# Test_Mux.net
KiCad netlist of a schematic drawn in Altium Designer
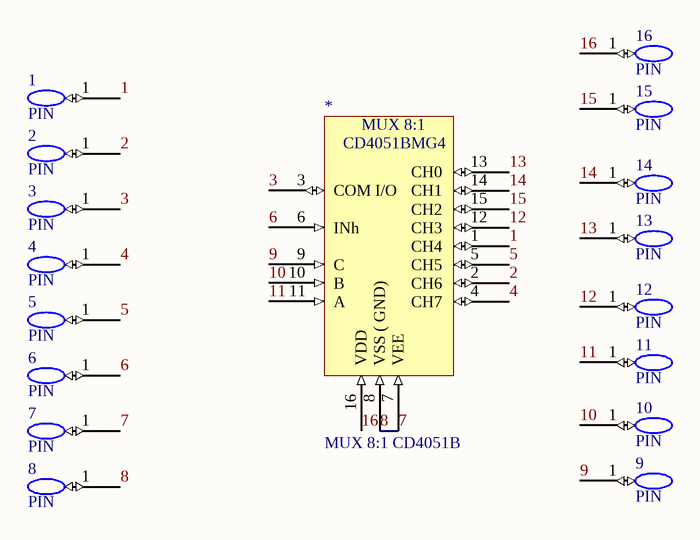
[diagram p0: Test Mux.SchDoc]

(export (version "E")
  (design (tool "Eeschema 10.0.6"))
  (components
    (comp (ref "*")
      (value "MUX 8:1 CD4051B")
      (footprint "MUX 8:1*")
      (libsource (lib "Carte Détéction Librairie") (part "MUX 8{colon}1 CD4051B"))
    )
    (comp (ref "1") (value "PIN") (footprint "TESTPOINT") (libsource (lib "ISEN_basics") (part "PIN")))
    (comp (ref "2") (value "PIN") (footprint "TESTPOINT") (libsource (lib "ISEN_basics") (part "PIN")))
    (comp (ref "3") (value "PIN") (footprint "TESTPOINT") (libsource (lib "ISEN_basics") (part "PIN")))
    (comp (ref "4") (value "PIN") (footprint "TESTPOINT") (libsource (lib "ISEN_basics") (part "PIN")))
    (comp (ref "5") (value "PIN") (footprint "TESTPOINT") (libsource (lib "ISEN_basics") (part "PIN")))
    (comp (ref "6") (value "PIN") (footprint "TESTPOINT") (libsource (lib "ISEN_basics") (part "PIN")))
    (comp (ref "7") (value "PIN") (footprint "TESTPOINT") (libsource (lib "ISEN_basics") (part "PIN")))
    (comp (ref "8") (value "PIN") (footprint "TESTPOINT") (libsource (lib "ISEN_basics") (part "PIN")))
    (comp (ref "9") (value "PIN") (footprint "TESTPOINT") (libsource (lib "ISEN_basics") (part "PIN")))
    (comp (ref "10") (value "PIN") (footprint "TESTPOINT") (libsource (lib "ISEN_basics") (part "PIN")))
    (comp (ref "11") (value "PIN") (footprint "TESTPOINT") (libsource (lib "ISEN_basics") (part "PIN")))
    (comp (ref "12") (value "PIN") (footprint "TESTPOINT") (libsource (lib "ISEN_basics") (part "PIN")))
    (comp (ref "13") (value "PIN") (footprint "TESTPOINT") (libsource (lib "ISEN_basics") (part "PIN")))
    (comp (ref "14") (value "PIN") (footprint "TESTPOINT") (libsource (lib "ISEN_basics") (part "PIN")))
    (comp (ref "15") (value "PIN") (footprint "TESTPOINT") (libsource (lib "ISEN_basics") (part "PIN")))
    (comp (ref "16") (value "PIN") (footprint "TESTPOINT") (libsource (lib "ISEN_basics") (part "PIN")))
  )
  (nets
    (net (code "1") (name "/1") (class "Default")
      (node (ref "*") (pin "1") (pinfunction "CH4_1") (pintype "bidirectional"))
      (node (ref "1") (pin "1") (pintype "bidirectional"))
    )
    (net (code "2") (name "/2") (class "Default")
      (node (ref "*") (pin "2") (pinfunction "CH6_2") (pintype "bidirectional"))
      (node (ref "2") (pin "1") (pintype "bidirectional"))
    )
    (net (code "3") (name "/3") (class "Default")
      (node (ref "*") (pin "3") (pinfunction "COM_I/O_3") (pintype "bidirectional"))
      (node (ref "3") (pin "1") (pintype "bidirectional"))
    )
    (net (code "4") (name "/4") (class "Default")
      (node (ref "*") (pin "4") (pinfunction "CH7_4") (pintype "bidirectional"))
      (node (ref "4") (pin "1") (pintype "bidirectional"))
    )
    (net (code "5") (name "/5") (class "Default")
      (node (ref "*") (pin "5") (pinfunction "CH5_5") (pintype "bidirectional"))
      (node (ref "5") (pin "1") (pintype "bidirectional"))
    )
    (net (code "6") (name "/6") (class "Default")
      (node (ref "*") (pin "6") (pinfunction "INh_6") (pintype "input"))
      (node (ref "6") (pin "1") (pintype "bidirectional"))
    )
    (net (code "7") (name "/7") (class "Default")
      (node (ref "*") (pin "7") (pinfunction "VEE_7") (pintype "input"))
      (node (ref "*") (pin "8") (pinfunction "VSS_(_GND)_8") (pintype "input"))
      (node (ref "7") (pin "1") (pintype "bidirectional"))
      (node (ref "8") (pin "1") (pintype "bidirectional"))
    )
    (net (code "8") (name "/9") (class "Default")
      (node (ref "*") (pin "9") (pinfunction "C_9") (pintype "input"))
      (node (ref "9") (pin "1") (pintype "bidirectional"))
    )
    (net (code "9") (name "/10") (class "Default")
      (node (ref "*") (pin "10") (pinfunction "B_10") (pintype "input"))
      (node (ref "10") (pin "1") (pintype "bidirectional"))
    )
    (net (code "10") (name "/11") (class "Default")
      (node (ref "*") (pin "11") (pinfunction "A_11") (pintype "input"))
      (node (ref "11") (pin "1") (pintype "bidirectional"))
    )
    (net (code "11") (name "/12") (class "Default")
      (node (ref "*") (pin "12") (pinfunction "CH3_12") (pintype "bidirectional"))
      (node (ref "12") (pin "1") (pintype "bidirectional"))
    )
    (net (code "12") (name "/13") (class "Default")
      (node (ref "*") (pin "13") (pinfunction "CH0_13") (pintype "bidirectional"))
      (node (ref "13") (pin "1") (pintype "bidirectional"))
    )
    (net (code "13") (name "/14") (class "Default")
      (node (ref "*") (pin "14") (pinfunction "CH1_14") (pintype "bidirectional"))
      (node (ref "14") (pin "1") (pintype "bidirectional"))
    )
    (net (code "14") (name "/15") (class "Default")
      (node (ref "*") (pin "15") (pinfunction "CH2_15") (pintype "bidirectional"))
      (node (ref "15") (pin "1") (pintype "bidirectional"))
    )
    (net (code "15") (name "/16") (class "Default")
      (node (ref "*") (pin "16") (pinfunction "VDD_16") (pintype "input"))
      (node (ref "16") (pin "1") (pintype "bidirectional"))
    )
  )
)
